# interstage_B2v2.net
KiCad netlist of a schematic drawn in EAGLE
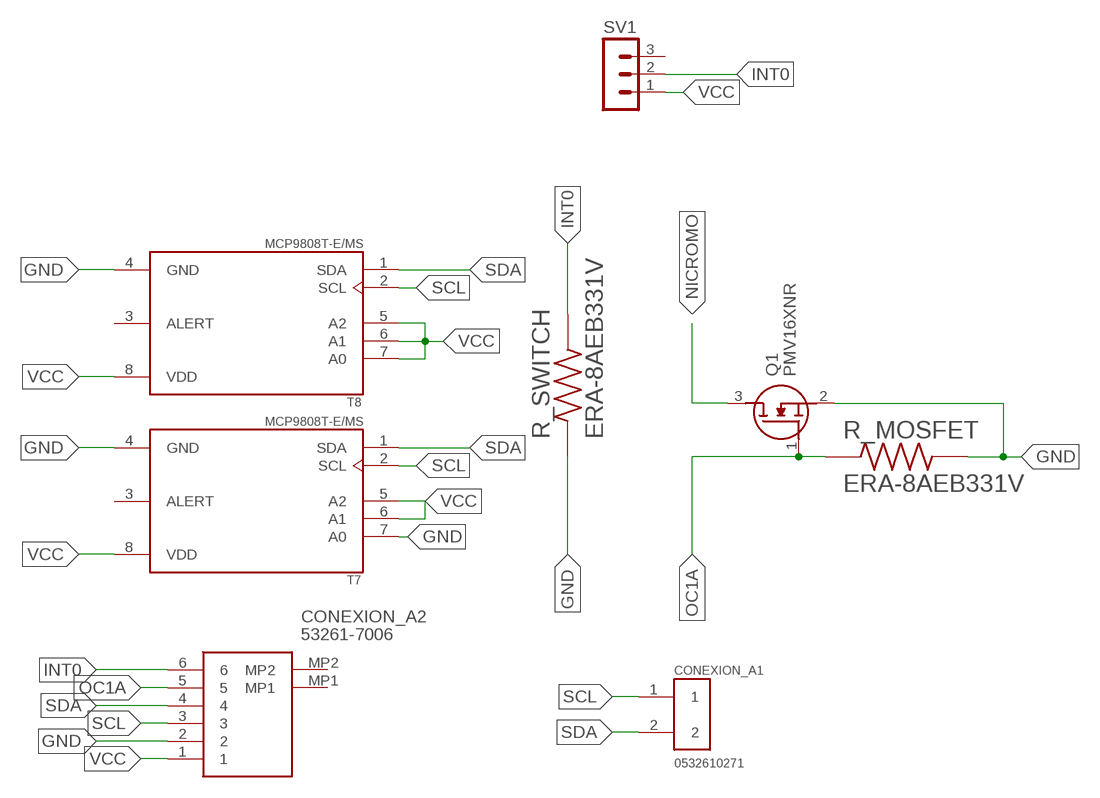
[diagram p0: schematic, sheet 1]

(export (version "E")
  (design (tool "Eeschema 10.0.6"))
  (components
    (comp (ref "CONEXION_A1")
      (value "0532610271")
      (footprint "eagle-import:MOLEX_0532610271")
      (fields (field (name "MF") "Molex"))
      (libsource (lib "eagle-import") (part "0532610271"))
    )
    (comp (ref "CONEXION_A2")
      (value "53261-7006")
      (footprint "eagle-import:532617006")
      (fields (field (name "MOUSER_PART_NUMBER") "538-53261-7006"))
      (libsource (lib "eagle-import") (part "53261-7006"))
    )
    (comp (ref "Q1")
      (value "PMV16XNR")
      (footprint "eagle-import:SOT95P230X110-3N")
      (fields (field (name "MOUSER_PART_NUMBER") "771-PMV16XNR"))
      (libsource (lib "eagle-import") (part "PMV16XNR"))
    )
    (comp (ref "R_MOSFET")
      (value "ERA-8AEB331V")
      (footprint "eagle-import:RESC3216X70N")
      (fields (field (name "DIGI-KEY_PART_NUMBER") "P330BCCT-ND") (field (name "MF") "Panasonic Electronic"))
      (libsource (lib "eagle-import") (part "ERA-8AEB331V"))
    )
    (comp (ref "R_SWITCH")
      (value "ERA-8AEB331V")
      (footprint "eagle-import:RESC3216X70N")
      (fields (field (name "DIGI-KEY_PART_NUMBER") "P330BCCT-ND") (field (name "MF") "Panasonic Electronic"))
      (libsource (lib "eagle-import") (part "ERA-8AEB331V"))
    )
    (comp (ref "SV1")
      (value "MA03-1")
      (footprint "eagle-import:MA03-1")
      (libsource (lib "eagle-import") (part "MA03-1"))
    )
    (comp (ref "T7")
      (value "MCP9808T-E/MS")
      (footprint "eagle-import:SOP65P490X110-8N")
      (fields (field (name "DIGI-KEY_PART_NUMBER") "MCP9808T-E/MSCT-ND") (field (name "MF") "Microchip"))
      (libsource (lib "eagle-import") (part "MCP9808T-E/MS"))
    )
    (comp (ref "T8")
      (value "MCP9808T-E/MS")
      (footprint "eagle-import:SOP65P490X110-8N")
      (fields (field (name "DIGI-KEY_PART_NUMBER") "MCP9808T-E/MSCT-ND") (field (name "MF") "Microchip"))
      (libsource (lib "eagle-import") (part "MCP9808T-E/MS"))
    )
  )
  (nets
    (net (code "1") (name "GND") (class "Default")
      (node (ref "CONEXION_A2") (pin "2") (pinfunction "2_2") (pintype "bidirectional"))
      (node (ref "Q1") (pin "2") (pinfunction "S_2") (pintype "bidirectional"))
      (node (ref "R_MOSFET") (pin "2") (pinfunction "2_2") (pintype "passive"))
      (node (ref "R_SWITCH") (pin "1") (pinfunction "1_1") (pintype "passive"))
      (node (ref "T7") (pin "4") (pinfunction "GND_4") (pintype "power_in"))
      (node (ref "T7") (pin "7") (pinfunction "A0_7") (pintype "input"))
      (node (ref "T8") (pin "4") (pinfunction "GND_4") (pintype "power_in"))
    )
    (net (code "2") (name "INT0") (class "Default")
      (node (ref "CONEXION_A2") (pin "6") (pinfunction "6_6") (pintype "bidirectional"))
      (node (ref "R_SWITCH") (pin "2") (pinfunction "2_2") (pintype "passive"))
      (node (ref "SV1") (pin "2") (pinfunction "2_2") (pintype "passive"))
    )
    (net (code "3") (name "NICROMO") (class "Default")
      (node (ref "Q1") (pin "3") (pinfunction "D_3") (pintype "bidirectional"))
    )
    (net (code "4") (name "OC1A") (class "Default")
      (node (ref "CONEXION_A2") (pin "5") (pinfunction "5_5") (pintype "bidirectional"))
      (node (ref "Q1") (pin "1") (pinfunction "G_1") (pintype "bidirectional"))
      (node (ref "R_MOSFET") (pin "1") (pinfunction "1_1") (pintype "passive"))
    )
    (net (code "5") (name "SCL") (class "Default")
      (node (ref "CONEXION_A1") (pin "1") (pinfunction "1_1") (pintype "passive"))
      (node (ref "CONEXION_A2") (pin "3") (pinfunction "3_3") (pintype "bidirectional"))
      (node (ref "T7") (pin "2") (pinfunction "SCL_2") (pintype "input"))
      (node (ref "T8") (pin "2") (pinfunction "SCL_2") (pintype "input"))
    )
    (net (code "6") (name "SDA") (class "Default")
      (node (ref "CONEXION_A1") (pin "2") (pinfunction "2_2") (pintype "passive"))
      (node (ref "CONEXION_A2") (pin "4") (pinfunction "4_4") (pintype "bidirectional"))
      (node (ref "T7") (pin "1") (pinfunction "SDA_1") (pintype "bidirectional"))
      (node (ref "T8") (pin "1") (pinfunction "SDA_1") (pintype "bidirectional"))
    )
    (net (code "7") (name "VCC") (class "Default")
      (node (ref "CONEXION_A2") (pin "1") (pinfunction "1_1") (pintype "bidirectional"))
      (node (ref "SV1") (pin "1") (pinfunction "1_1") (pintype "passive"))
      (node (ref "T7") (pin "5") (pinfunction "A2_5") (pintype "input"))
      (node (ref "T7") (pin "6") (pinfunction "A1_6") (pintype "input"))
      (node (ref "T7") (pin "8") (pinfunction "VDD_8") (pintype "power_in"))
      (node (ref "T8") (pin "5") (pinfunction "A2_5") (pintype "input"))
      (node (ref "T8") (pin "6") (pinfunction "A1_6") (pintype "input"))
      (node (ref "T8") (pin "7") (pinfunction "A0_7") (pintype "input"))
      (node (ref "T8") (pin "8") (pinfunction "VDD_8") (pintype "power_in"))
    )
    (net (code "8") (name "unconnected-(CONEXION_A2-PadMP1)") (class "Default")
      (node (ref "CONEXION_A2") (pin "MP1") (pinfunction "MP1_MP1") (pintype "bidirectional"))
    )
    (net (code "9") (name "unconnected-(CONEXION_A2-PadMP2)") (class "Default")
      (node (ref "CONEXION_A2") (pin "MP2") (pinfunction "MP2_MP2") (pintype "bidirectional"))
    )
    (net (code "10") (name "unconnected-(SV1-Pad3)") (class "Default")
      (node (ref "SV1") (pin "3") (pinfunction "3_3") (pintype "passive"))
    )
    (net (code "11") (name "unconnected-(T7-ALERT-Pad3)") (class "Default")
      (node (ref "T7") (pin "3") (pinfunction "ALERT_3") (pintype "output"))
    )
    (net (code "12") (name "unconnected-(T8-ALERT-Pad3)") (class "Default")
      (node (ref "T8") (pin "3") (pinfunction "ALERT_3") (pintype "output"))
    )
  )
)
